# TXS0102_I2C_Bus_Voltage_Translator.net
KiCad netlist of a schematic drawn in Altium Designer
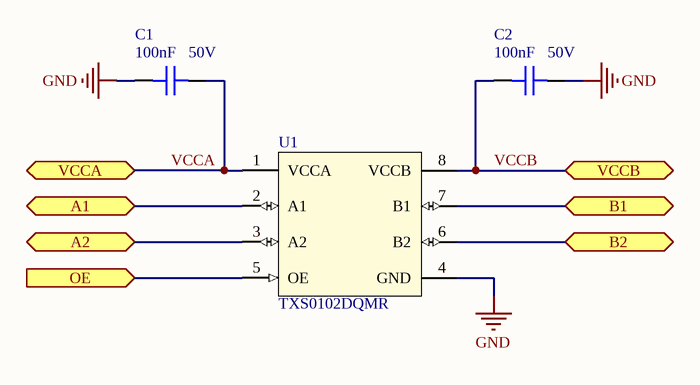
[diagram p0: TXS0102_I2C_Bus_Voltage_Translator.SchDoc]

(export (version "E")
  (design (tool "Eeschema 10.0.6"))
  (components
    (comp (ref "C1")
      (value "CGA2B3X7R1H104K050BB")
      (footprint "C0402")
      (description "0.1µF ±10% 50V Ceramic Capacitor X7R 0402 (1005 Metric)")
      (fields
        (field (name "MANUFACTURER") "TDK")
        (field (name "TOLERANCE") "10%")
        (field (name "CAPACITANCE") "100nF")
        (field (name "VOLTAGE") "50V")
      )
      (libsource (lib "capacitors_smd") (part "CAP CER 0.1UF 50V X7R 0402"))
    )
    (comp (ref "C2")
      (value "CGA2B3X7R1H104K050BB")
      (footprint "C0402")
      (description "0.1µF ±10% 50V Ceramic Capacitor X7R 0402 (1005 Metric)")
      (fields
        (field (name "MANUFACTURER") "TDK")
        (field (name "TOLERANCE") "10%")
        (field (name "CAPACITANCE") "100nF")
        (field (name "VOLTAGE") "50V")
      )
      (libsource (lib "capacitors_smd") (part "CAP CER 0.1UF 50V X7R 0402"))
    )
    (comp (ref "U1")
      (value "TXS0102DQMR")
      (footprint "DQM8")
      (description "2-Bit Bidirectional Voltage-Level Translator for Open-Drain Application")
      (fields (field (name "MANUFACTURER") "Texas Instruments"))
      (libsource (lib "BLDC_Moto_Driver") (part "IC TXS0102 TRNSLTR BIDIRECTIONAL 8X2SON"))
    )
  )
  (nets
    (net (code "1") (name "/A1") (class "Default")
      (node (ref "U1") (pin "2") (pinfunction "A1_2") (pintype "bidirectional"))
    )
    (net (code "2") (name "/A2") (class "Default")
      (node (ref "U1") (pin "3") (pinfunction "A2_3") (pintype "bidirectional"))
    )
    (net (code "3") (name "/B1") (class "Default")
      (node (ref "U1") (pin "7") (pinfunction "B1_7") (pintype "bidirectional"))
    )
    (net (code "4") (name "/B2") (class "Default")
      (node (ref "U1") (pin "6") (pinfunction "B2_6") (pintype "bidirectional"))
    )
    (net (code "5") (name "/OE") (class "Default")
      (node (ref "U1") (pin "5") (pinfunction "OE_5") (pintype "input"))
    )
    (net (code "6") (name "/VCCA") (class "Default")
      (node (ref "C1") (pin "1") (pinfunction "1_1") (pintype "passive"))
      (node (ref "U1") (pin "1") (pinfunction "VCCA_1") (pintype "power_in"))
    )
    (net (code "7") (name "/VCCB") (class "Default")
      (node (ref "C2") (pin "2") (pinfunction "2_2") (pintype "passive"))
      (node (ref "U1") (pin "8") (pinfunction "VCCB_8") (pintype "power_in"))
    )
    (net (code "8") (name "GND") (class "Default")
      (node (ref "C1") (pin "2") (pinfunction "2_2") (pintype "passive"))
      (node (ref "C2") (pin "1") (pinfunction "1_1") (pintype "passive"))
      (node (ref "U1") (pin "4") (pinfunction "GND_4") (pintype "power_in"))
    )
  )
)
